# PCI_Express_16765X6890_98PIN_Low_profile.net
KiCad netlist of a schematic drawn in Altium Designer
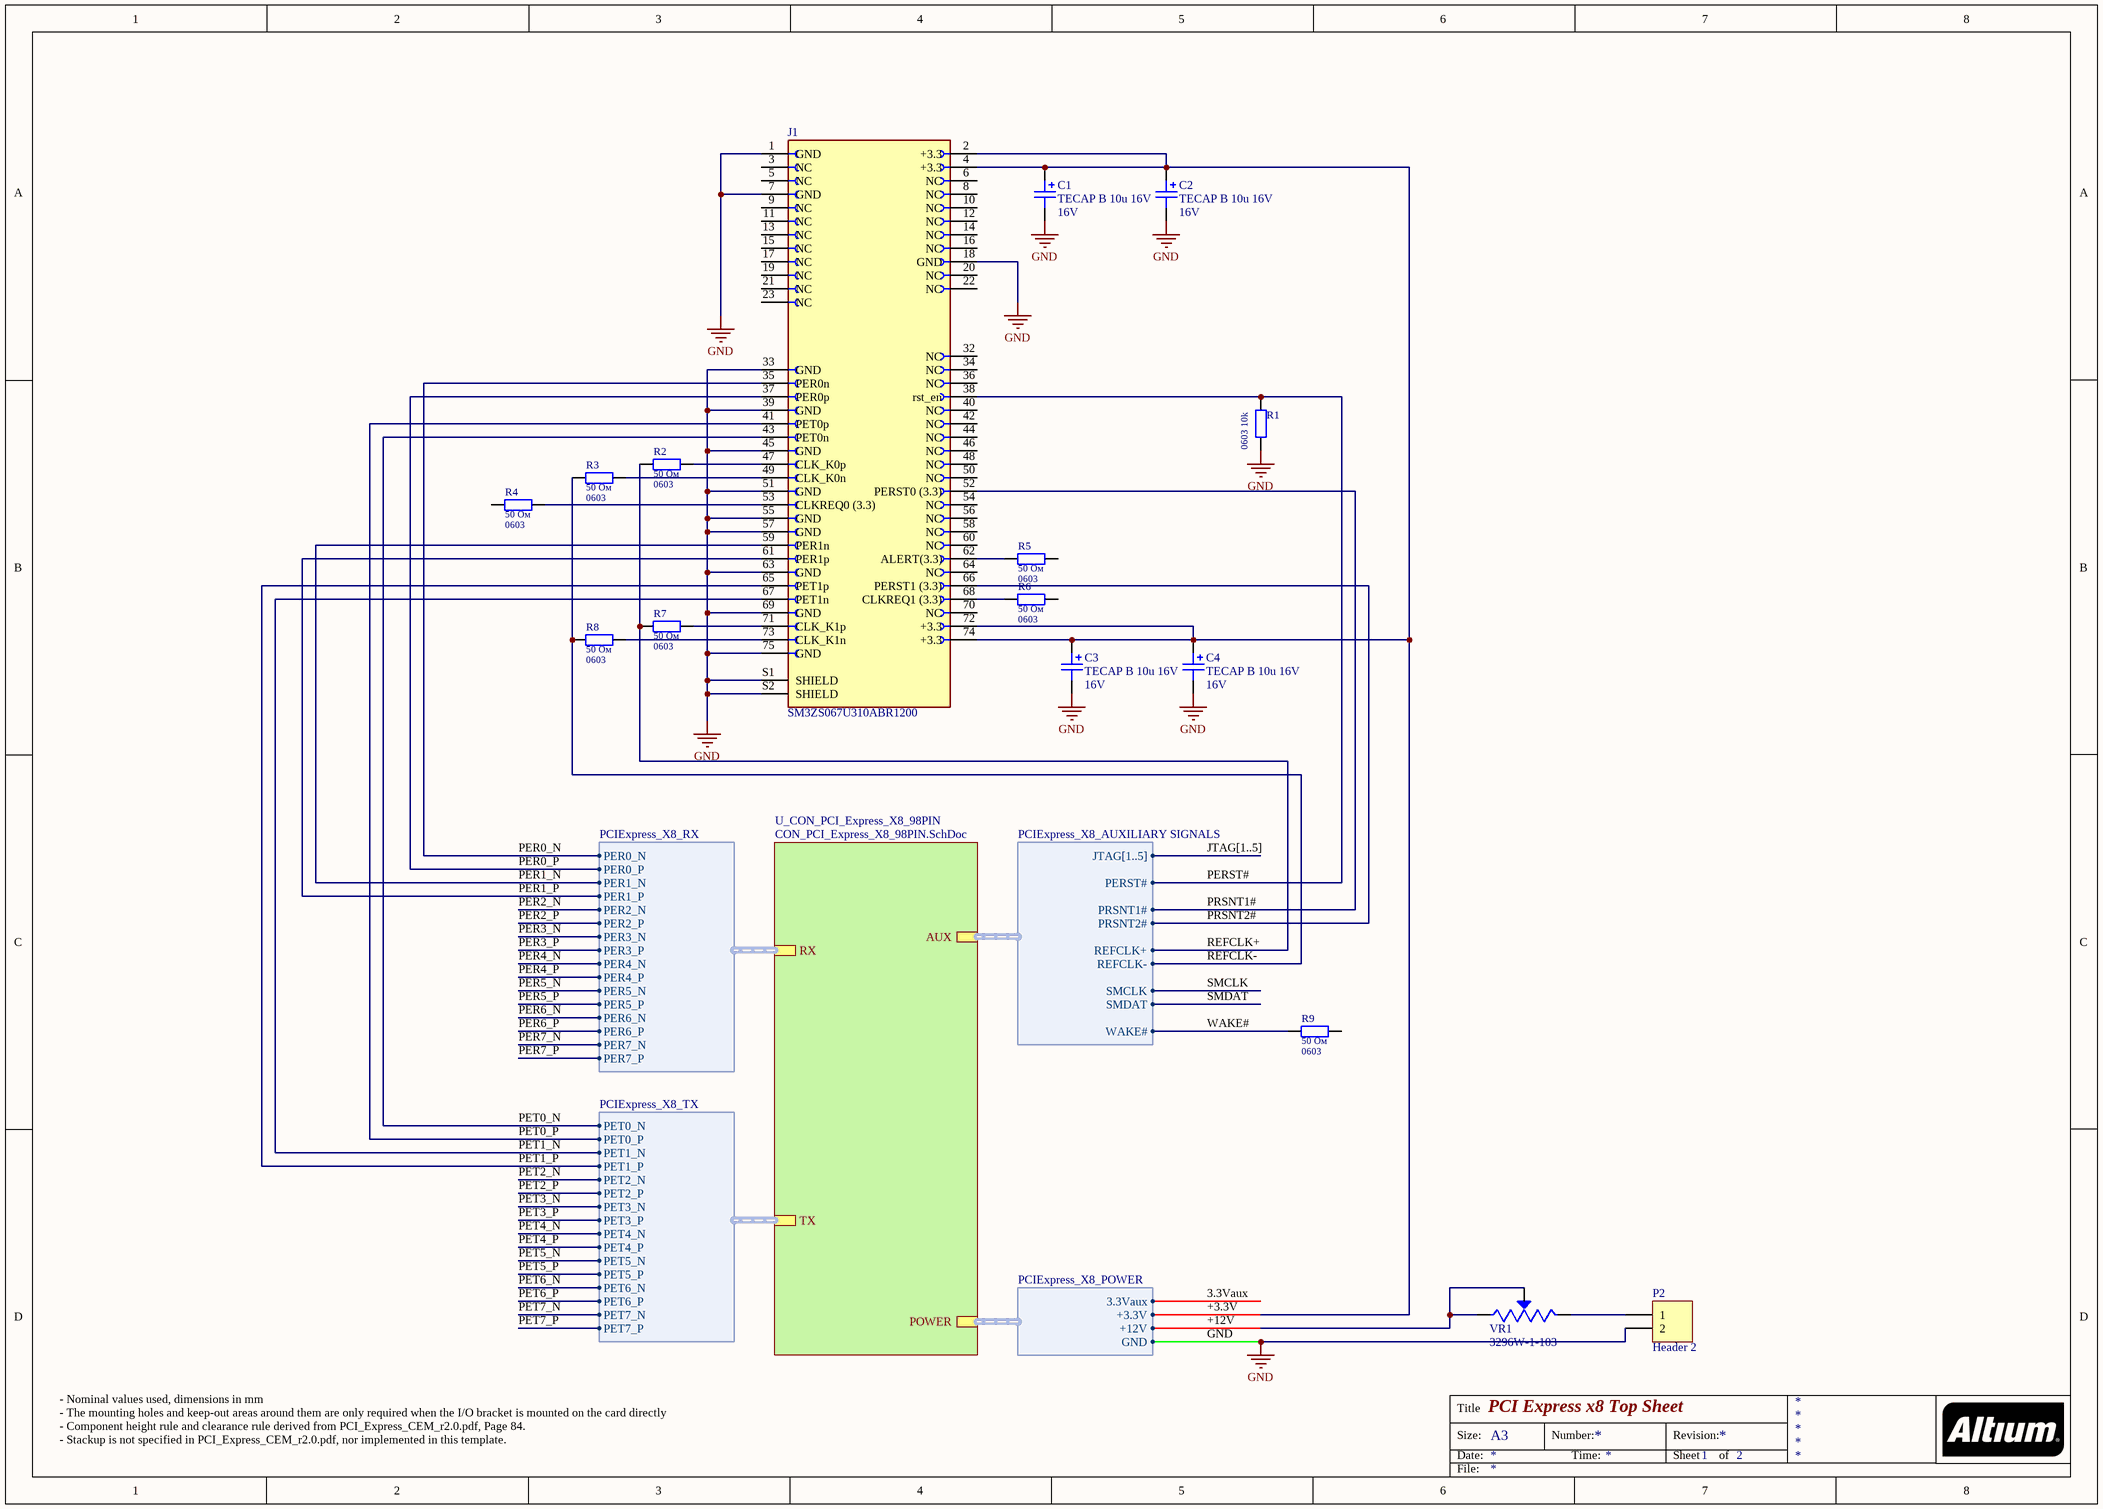
[diagram p0: PCI Express_16765X6890_98PIN_Low profile.schdoc]

(export (version "E")
  (design (tool "Eeschema 10.0.6"))
  (components
    (comp (ref "C1")
      (value "TECAP B 10u 16V")
      (footprint "TECAP B")
      (description "Solid Tantalum Surface Mount Capacitors")
      (fields (field (name "VOLTAGE") "16V"))
      (libsource (lib "RCL") (part "Cap T"))
    )
    (comp (ref "C2")
      (value "TECAP B 10u 16V")
      (footprint "TECAP B")
      (description "Solid Tantalum Surface Mount Capacitors")
      (fields (field (name "VOLTAGE") "16V"))
      (libsource (lib "RCL") (part "Cap T"))
    )
    (comp (ref "C3")
      (value "TECAP B 10u 16V")
      (footprint "TECAP B")
      (description "Solid Tantalum Surface Mount Capacitors")
      (fields (field (name "VOLTAGE") "16V"))
      (libsource (lib "RCL") (part "Cap T"))
    )
    (comp (ref "C4")
      (value "TECAP B 10u 16V")
      (footprint "TECAP B")
      (description "Solid Tantalum Surface Mount Capacitors")
      (fields (field (name "VOLTAGE") "16V"))
      (libsource (lib "RCL") (part "Cap T"))
    )
    (comp (ref "J1")
      (value "SM3ZS067U310ABR1200")
      (footprint "JAE_SM3ZS067U310ABR1200")
      (description "67 Position Female Connector M.2 (NGFF) Mini Card Gold 0.020 (0.50mm)")
      (fields (field (name "MF") "JAE Electronics"))
      (libsource (lib "SM3ZS067U310ABR1200") (part "SM3ZS067U310ABR1200"))
    )
    (comp (ref "P2")
      (value "Header 2")
      (footprint "HDR1X2")
      (description "Header, 2-Pin")
      (fields (field (name "PUBLISHER") "Altium Limited"))
      (libsource (lib "Miscellaneous Connectors") (part "Header 2"))
    )
    (comp (ref "R1")
      (value "0603 10k")
      (footprint "RESCHIP0603")
      (description "Resistor")
      (libsource (lib "") (part "Res_1"))
    )
    (comp (ref "R2")
      (value "50 Ом")
      (footprint "RESCHIP0603")
      (description "Резистор SMD R0603")
      (fields (field (name "TOLERANCE") "%") (field (name "TYPE") "0603"))
      (libsource (lib "RCL") (part "Res"))
    )
    (comp (ref "R3")
      (value "50 Ом")
      (footprint "RESCHIP0603")
      (description "Резистор SMD R0603")
      (fields (field (name "TOLERANCE") "%") (field (name "TYPE") "0603"))
      (libsource (lib "RCL") (part "Res"))
    )
    (comp (ref "R4")
      (value "50 Ом")
      (footprint "RESCHIP0603")
      (description "Резистор SMD R0603")
      (fields (field (name "TOLERANCE") "%") (field (name "TYPE") "0603"))
      (libsource (lib "RCL") (part "Res"))
    )
    (comp (ref "R5")
      (value "50 Ом")
      (footprint "RESCHIP0603")
      (description "Резистор SMD R0603")
      (fields (field (name "TOLERANCE") "%") (field (name "TYPE") "0603"))
      (libsource (lib "RCL") (part "Res"))
    )
    (comp (ref "R6")
      (value "50 Ом")
      (footprint "RESCHIP0603")
      (description "Резистор SMD R0603")
      (fields (field (name "TOLERANCE") "%") (field (name "TYPE") "0603"))
      (libsource (lib "RCL") (part "Res"))
    )
    (comp (ref "R7")
      (value "50 Ом")
      (footprint "RESCHIP0603")
      (description "Резистор SMD R0603")
      (fields (field (name "TOLERANCE") "%") (field (name "TYPE") "0603"))
      (libsource (lib "RCL") (part "Res"))
    )
    (comp (ref "R8")
      (value "50 Ом")
      (footprint "RESCHIP0603")
      (description "Резистор SMD R0603")
      (fields (field (name "TOLERANCE") "%") (field (name "TYPE") "0603"))
      (libsource (lib "RCL") (part "Res"))
    )
    (comp (ref "R9")
      (value "50 Ом")
      (footprint "RESCHIP0603")
      (description "Резистор SMD R0603")
      (fields (field (name "TOLERANCE") "%") (field (name "TYPE") "0603"))
      (libsource (lib "RCL") (part "Res"))
    )
    (comp (ref "VR1")
      (value "3296W-1-103")
      (footprint "TRIM_3296W-1-103")
      (fields (field (name "MF") "Bourns"))
      (libsource (lib "3296W-1-103") (part "3296W-1-103"))
    )
  )
  (nets
    (net (code "5") (name "/+3.3V") (class "Default")
      (node (ref "C1") (pin "1") (pinfunction "1_1") (pintype "passive"))
      (node (ref "C2") (pin "1") (pinfunction "1_1") (pintype "passive"))
      (node (ref "C3") (pin "1") (pinfunction "1_1") (pintype "passive"))
      (node (ref "C4") (pin "1") (pinfunction "1_1") (pintype "passive"))
      (node (ref "J1") (pin "2") (pinfunction "+3.3_2") (pintype "passive"))
      (node (ref "J1") (pin "4") (pinfunction "+3.3_4") (pintype "passive"))
      (node (ref "J1") (pin "72") (pinfunction "+3.3_72") (pintype "passive"))
      (node (ref "J1") (pin "74") (pinfunction "+3.3_74") (pintype "passive"))
    )
    (net (code "6") (name "/+12V") (class "Default")
      (node (ref "VR1") (pin "1") (pinfunction "CCW_1") (pintype "passive"))
      (node (ref "VR1") (pin "2") (pinfunction "WIPER_2") (pintype "passive"))
    )
    (net (code "9") (name "/PER0_N") (class "Default")
      (node (ref "J1") (pin "35") (pinfunction "PER0n_35") (pintype "passive"))
    )
    (net (code "10") (name "/PER0_P") (class "Default")
      (node (ref "J1") (pin "37") (pinfunction "PER0p_37") (pintype "passive"))
    )
    (net (code "11") (name "/PER1_N") (class "Default")
      (node (ref "J1") (pin "59") (pinfunction "PER1n_59") (pintype "passive"))
    )
    (net (code "12") (name "/PER1_P") (class "Default")
      (node (ref "J1") (pin "61") (pinfunction "PER1p_61") (pintype "passive"))
    )
    (net (code "25") (name "/PERST#") (class "Default")
      (node (ref "J1") (pin "38") (pinfunction "rst_en_38") (pintype "passive"))
      (node (ref "R1") (pin "1") (pinfunction "1_1") (pintype "passive"))
    )
    (net (code "26") (name "/PET0_N") (class "Default")
      (node (ref "J1") (pin "43") (pinfunction "PET0n_43") (pintype "passive"))
    )
    (net (code "27") (name "/PET0_P") (class "Default")
      (node (ref "J1") (pin "41") (pinfunction "PET0p_41") (pintype "passive"))
    )
    (net (code "28") (name "/PET1_N") (class "Default")
      (node (ref "J1") (pin "67") (pinfunction "PET1n_67") (pintype "passive"))
    )
    (net (code "29") (name "/PET1_P") (class "Default")
      (node (ref "J1") (pin "65") (pinfunction "PET1p_65") (pintype "passive"))
    )
    (net (code "42") (name "/PRSNT1#") (class "Default")
      (node (ref "J1") (pin "52") (pinfunction "PERST0_(3.3)_52") (pintype "passive"))
    )
    (net (code "43") (name "/PRSNT2#") (class "Default")
      (node (ref "J1") (pin "66") (pinfunction "PERST1_(3.3)_66") (pintype "passive"))
    )
    (net (code "44") (name "/REFCLK+") (class "Default")
      (node (ref "R2") (pin "1") (pinfunction "1_1") (pintype "passive"))
      (node (ref "R7") (pin "1") (pinfunction "1_1") (pintype "passive"))
    )
    (net (code "45") (name "/REFCLK-") (class "Default")
      (node (ref "R3") (pin "1") (pinfunction "1_1") (pintype "passive"))
      (node (ref "R8") (pin "1") (pinfunction "1_1") (pintype "passive"))
    )
    (net (code "48") (name "/WAKE#") (class "Default")
      (node (ref "R9") (pin "1") (pinfunction "1_1") (pintype "passive"))
    )
    (net (code "53") (name "GND") (class "Default")
      (node (ref "C1") (pin "2") (pinfunction "2_2") (pintype "passive"))
      (node (ref "C2") (pin "2") (pinfunction "2_2") (pintype "passive"))
      (node (ref "C3") (pin "2") (pinfunction "2_2") (pintype "passive"))
      (node (ref "C4") (pin "2") (pinfunction "2_2") (pintype "passive"))
      (node (ref "J1") (pin "1") (pinfunction "GND_1") (pintype "passive"))
      (node (ref "J1") (pin "18") (pinfunction "GND_18") (pintype "passive"))
      (node (ref "J1") (pin "33") (pinfunction "GND_33") (pintype "passive"))
      (node (ref "J1") (pin "39") (pinfunction "GND_39") (pintype "passive"))
      (node (ref "J1") (pin "45") (pinfunction "GND_45") (pintype "passive"))
      (node (ref "J1") (pin "51") (pinfunction "GND_51") (pintype "passive"))
      (node (ref "J1") (pin "55") (pinfunction "GND_55") (pintype "passive"))
      (node (ref "J1") (pin "57") (pinfunction "GND_57") (pintype "passive"))
      (node (ref "J1") (pin "63") (pinfunction "GND_63") (pintype "passive"))
      (node (ref "J1") (pin "69") (pinfunction "GND_69") (pintype "passive"))
      (node (ref "J1") (pin "7") (pinfunction "GND_7") (pintype "passive"))
      (node (ref "J1") (pin "75") (pinfunction "GND_75") (pintype "passive"))
      (node (ref "J1") (pin "S1") (pinfunction "SHIELD_S1") (pintype "passive"))
      (node (ref "J1") (pin "S2") (pinfunction "SHIELD_S2") (pintype "passive"))
      (node (ref "P2") (pin "2") (pinfunction "2_2") (pintype "passive"))
      (node (ref "R1") (pin "2") (pinfunction "2_2") (pintype "passive"))
    )
    (net (code "54") (name "Net-(J1-ALERT(3.3))") (class "Default")
      (node (ref "J1") (pin "62") (pinfunction "ALERT(3.3)_62") (pintype "passive"))
      (node (ref "R5") (pin "1") (pinfunction "1_1") (pintype "passive"))
    )
    (net (code "55") (name "Net-(J1-CLKREQ0_(3.3))") (class "Default")
      (node (ref "J1") (pin "53") (pinfunction "CLKREQ0_(3.3)_53") (pintype "passive"))
      (node (ref "R4") (pin "2") (pinfunction "2_2") (pintype "passive"))
    )
    (net (code "56") (name "Net-(J1-CLKREQ1_(3.3))") (class "Default")
      (node (ref "J1") (pin "68") (pinfunction "CLKREQ1_(3.3)_68") (pintype "passive"))
      (node (ref "R6") (pin "1") (pinfunction "1_1") (pintype "passive"))
    )
    (net (code "57") (name "Net-(J1-CLK_K0n)") (class "Default")
      (node (ref "J1") (pin "49") (pinfunction "CLK_K0n_49") (pintype "passive"))
      (node (ref "R3") (pin "2") (pinfunction "2_2") (pintype "passive"))
    )
    (net (code "58") (name "Net-(J1-CLK_K0p)") (class "Default")
      (node (ref "J1") (pin "47") (pinfunction "CLK_K0p_47") (pintype "passive"))
      (node (ref "R2") (pin "2") (pinfunction "2_2") (pintype "passive"))
    )
    (net (code "59") (name "Net-(J1-CLK_K1n)") (class "Default")
      (node (ref "J1") (pin "73") (pinfunction "CLK_K1n_73") (pintype "passive"))
      (node (ref "R8") (pin "2") (pinfunction "2_2") (pintype "passive"))
    )
    (net (code "60") (name "Net-(J1-CLK_K1p)") (class "Default")
      (node (ref "J1") (pin "71") (pinfunction "CLK_K1p_71") (pintype "passive"))
      (node (ref "R7") (pin "2") (pinfunction "2_2") (pintype "passive"))
    )
    (net (code "61") (name "Net-(VR1-CW)") (class "Default")
      (node (ref "P2") (pin "1") (pinfunction "1_1") (pintype "passive"))
      (node (ref "VR1") (pin "3") (pinfunction "CW_3") (pintype "passive"))
    )
    (net (code "62") (name "unconnected-(J1-NC-Pad3)") (class "Default")
      (node (ref "J1") (pin "3") (pinfunction "NC_3") (pintype "passive"))
    )
    (net (code "63") (name "unconnected-(J1-NC-Pad5)") (class "Default")
      (node (ref "J1") (pin "5") (pinfunction "NC_5") (pintype "passive"))
    )
    (net (code "64") (name "unconnected-(J1-NC-Pad6)") (class "Default")
      (node (ref "J1") (pin "6") (pinfunction "NC_6") (pintype "passive"))
    )
    (net (code "65") (name "unconnected-(J1-NC-Pad8)") (class "Default")
      (node (ref "J1") (pin "8") (pinfunction "NC_8") (pintype "passive"))
    )
    (net (code "66") (name "unconnected-(J1-NC-Pad9)") (class "Default")
      (node (ref "J1") (pin "9") (pinfunction "NC_9") (pintype "passive"))
    )
    (net (code "67") (name "unconnected-(J1-NC-Pad10)") (class "Default")
      (node (ref "J1") (pin "10") (pinfunction "NC_10") (pintype "passive"))
    )
    (net (code "68") (name "unconnected-(J1-NC-Pad11)") (class "Default")
      (node (ref "J1") (pin "11") (pinfunction "NC_11") (pintype "passive"))
    )
    (net (code "69") (name "unconnected-(J1-NC-Pad12)") (class "Default")
      (node (ref "J1") (pin "12") (pinfunction "NC_12") (pintype "passive"))
    )
    (net (code "70") (name "unconnected-(J1-NC-Pad13)") (class "Default")
      (node (ref "J1") (pin "13") (pinfunction "NC_13") (pintype "passive"))
    )
    (net (code "71") (name "unconnected-(J1-NC-Pad14)") (class "Default")
      (node (ref "J1") (pin "14") (pinfunction "NC_14") (pintype "passive"))
    )
    (net (code "72") (name "unconnected-(J1-NC-Pad15)") (class "Default")
      (node (ref "J1") (pin "15") (pinfunction "NC_15") (pintype "passive"))
    )
    (net (code "73") (name "unconnected-(J1-NC-Pad16)") (class "Default")
      (node (ref "J1") (pin "16") (pinfunction "NC_16") (pintype "passive"))
    )
    (net (code "74") (name "unconnected-(J1-NC-Pad17)") (class "Default")
      (node (ref "J1") (pin "17") (pinfunction "NC_17") (pintype "passive"))
    )
    (net (code "75") (name "unconnected-(J1-NC-Pad19)") (class "Default")
      (node (ref "J1") (pin "19") (pinfunction "NC_19") (pintype "passive"))
    )
    (net (code "76") (name "unconnected-(J1-NC-Pad20)") (class "Default")
      (node (ref "J1") (pin "20") (pinfunction "NC_20") (pintype "passive"))
    )
    (net (code "77") (name "unconnected-(J1-NC-Pad21)") (class "Default")
      (node (ref "J1") (pin "21") (pinfunction "NC_21") (pintype "passive"))
    )
    (net (code "78") (name "unconnected-(J1-NC-Pad22)") (class "Default")
      (node (ref "J1") (pin "22") (pinfunction "NC_22") (pintype "passive"))
    )
    (net (code "79") (name "unconnected-(J1-NC-Pad23)") (class "Default")
      (node (ref "J1") (pin "23") (pinfunction "NC_23") (pintype "passive"))
    )
    (net (code "80") (name "unconnected-(J1-NC-Pad32)") (class "Default")
      (node (ref "J1") (pin "32") (pinfunction "NC_32") (pintype "passive"))
    )
    (net (code "81") (name "unconnected-(J1-NC-Pad34)") (class "Default")
      (node (ref "J1") (pin "34") (pinfunction "NC_34") (pintype "passive"))
    )
    (net (code "82") (name "unconnected-(J1-NC-Pad36)") (class "Default")
      (node (ref "J1") (pin "36") (pinfunction "NC_36") (pintype "passive"))
    )
    (net (code "83") (name "unconnected-(J1-NC-Pad40)") (class "Default")
      (node (ref "J1") (pin "40") (pinfunction "NC_40") (pintype "passive"))
    )
    (net (code "84") (name "unconnected-(J1-NC-Pad42)") (class "Default")
      (node (ref "J1") (pin "42") (pinfunction "NC_42") (pintype "passive"))
    )
    (net (code "85") (name "unconnected-(J1-NC-Pad44)") (class "Default")
      (node (ref "J1") (pin "44") (pinfunction "NC_44") (pintype "passive"))
    )
    (net (code "86") (name "unconnected-(J1-NC-Pad46)") (class "Default")
      (node (ref "J1") (pin "46") (pinfunction "NC_46") (pintype "passive"))
    )
    (net (code "87") (name "unconnected-(J1-NC-Pad48)") (class "Default")
      (node (ref "J1") (pin "48") (pinfunction "NC_48") (pintype "passive"))
    )
    (net (code "88") (name "unconnected-(J1-NC-Pad50)") (class "Default")
      (node (ref "J1") (pin "50") (pinfunction "NC_50") (pintype "passive"))
    )
    (net (code "89") (name "unconnected-(J1-NC-Pad54)") (class "Default")
      (node (ref "J1") (pin "54") (pinfunction "NC_54") (pintype "passive"))
    )
    (net (code "90") (name "unconnected-(J1-NC-Pad56)") (class "Default")
      (node (ref "J1") (pin "56") (pinfunction "NC_56") (pintype "passive"))
    )
    (net (code "91") (name "unconnected-(J1-NC-Pad58)") (class "Default")
      (node (ref "J1") (pin "58") (pinfunction "NC_58") (pintype "passive"))
    )
    (net (code "92") (name "unconnected-(J1-NC-Pad60)") (class "Default")
      (node (ref "J1") (pin "60") (pinfunction "NC_60") (pintype "passive"))
    )
    (net (code "93") (name "unconnected-(J1-NC-Pad64)") (class "Default")
      (node (ref "J1") (pin "64") (pinfunction "NC_64") (pintype "passive"))
    )
    (net (code "94") (name "unconnected-(J1-NC-Pad70)") (class "Default")
      (node (ref "J1") (pin "70") (pinfunction "NC_70") (pintype "passive"))
    )
    (net (code "95") (name "unconnected-(R4-Pad1)") (class "Default")
      (node (ref "R4") (pin "1") (pinfunction "1_1") (pintype "passive"))
    )
    (net (code "96") (name "unconnected-(R5-Pad2)") (class "Default")
      (node (ref "R5") (pin "2") (pinfunction "2_2") (pintype "passive"))
    )
    (net (code "97") (name "unconnected-(R6-Pad2)") (class "Default")
      (node (ref "R6") (pin "2") (pinfunction "2_2") (pintype "passive"))
    )
    (net (code "98") (name "unconnected-(R9-Pad2)") (class "Default")
      (node (ref "R9") (pin "2") (pinfunction "2_2") (pintype "passive"))
    )
  )
)
